# BaseModule_v8.net
KiCad netlist of a schematic drawn in EAGLE
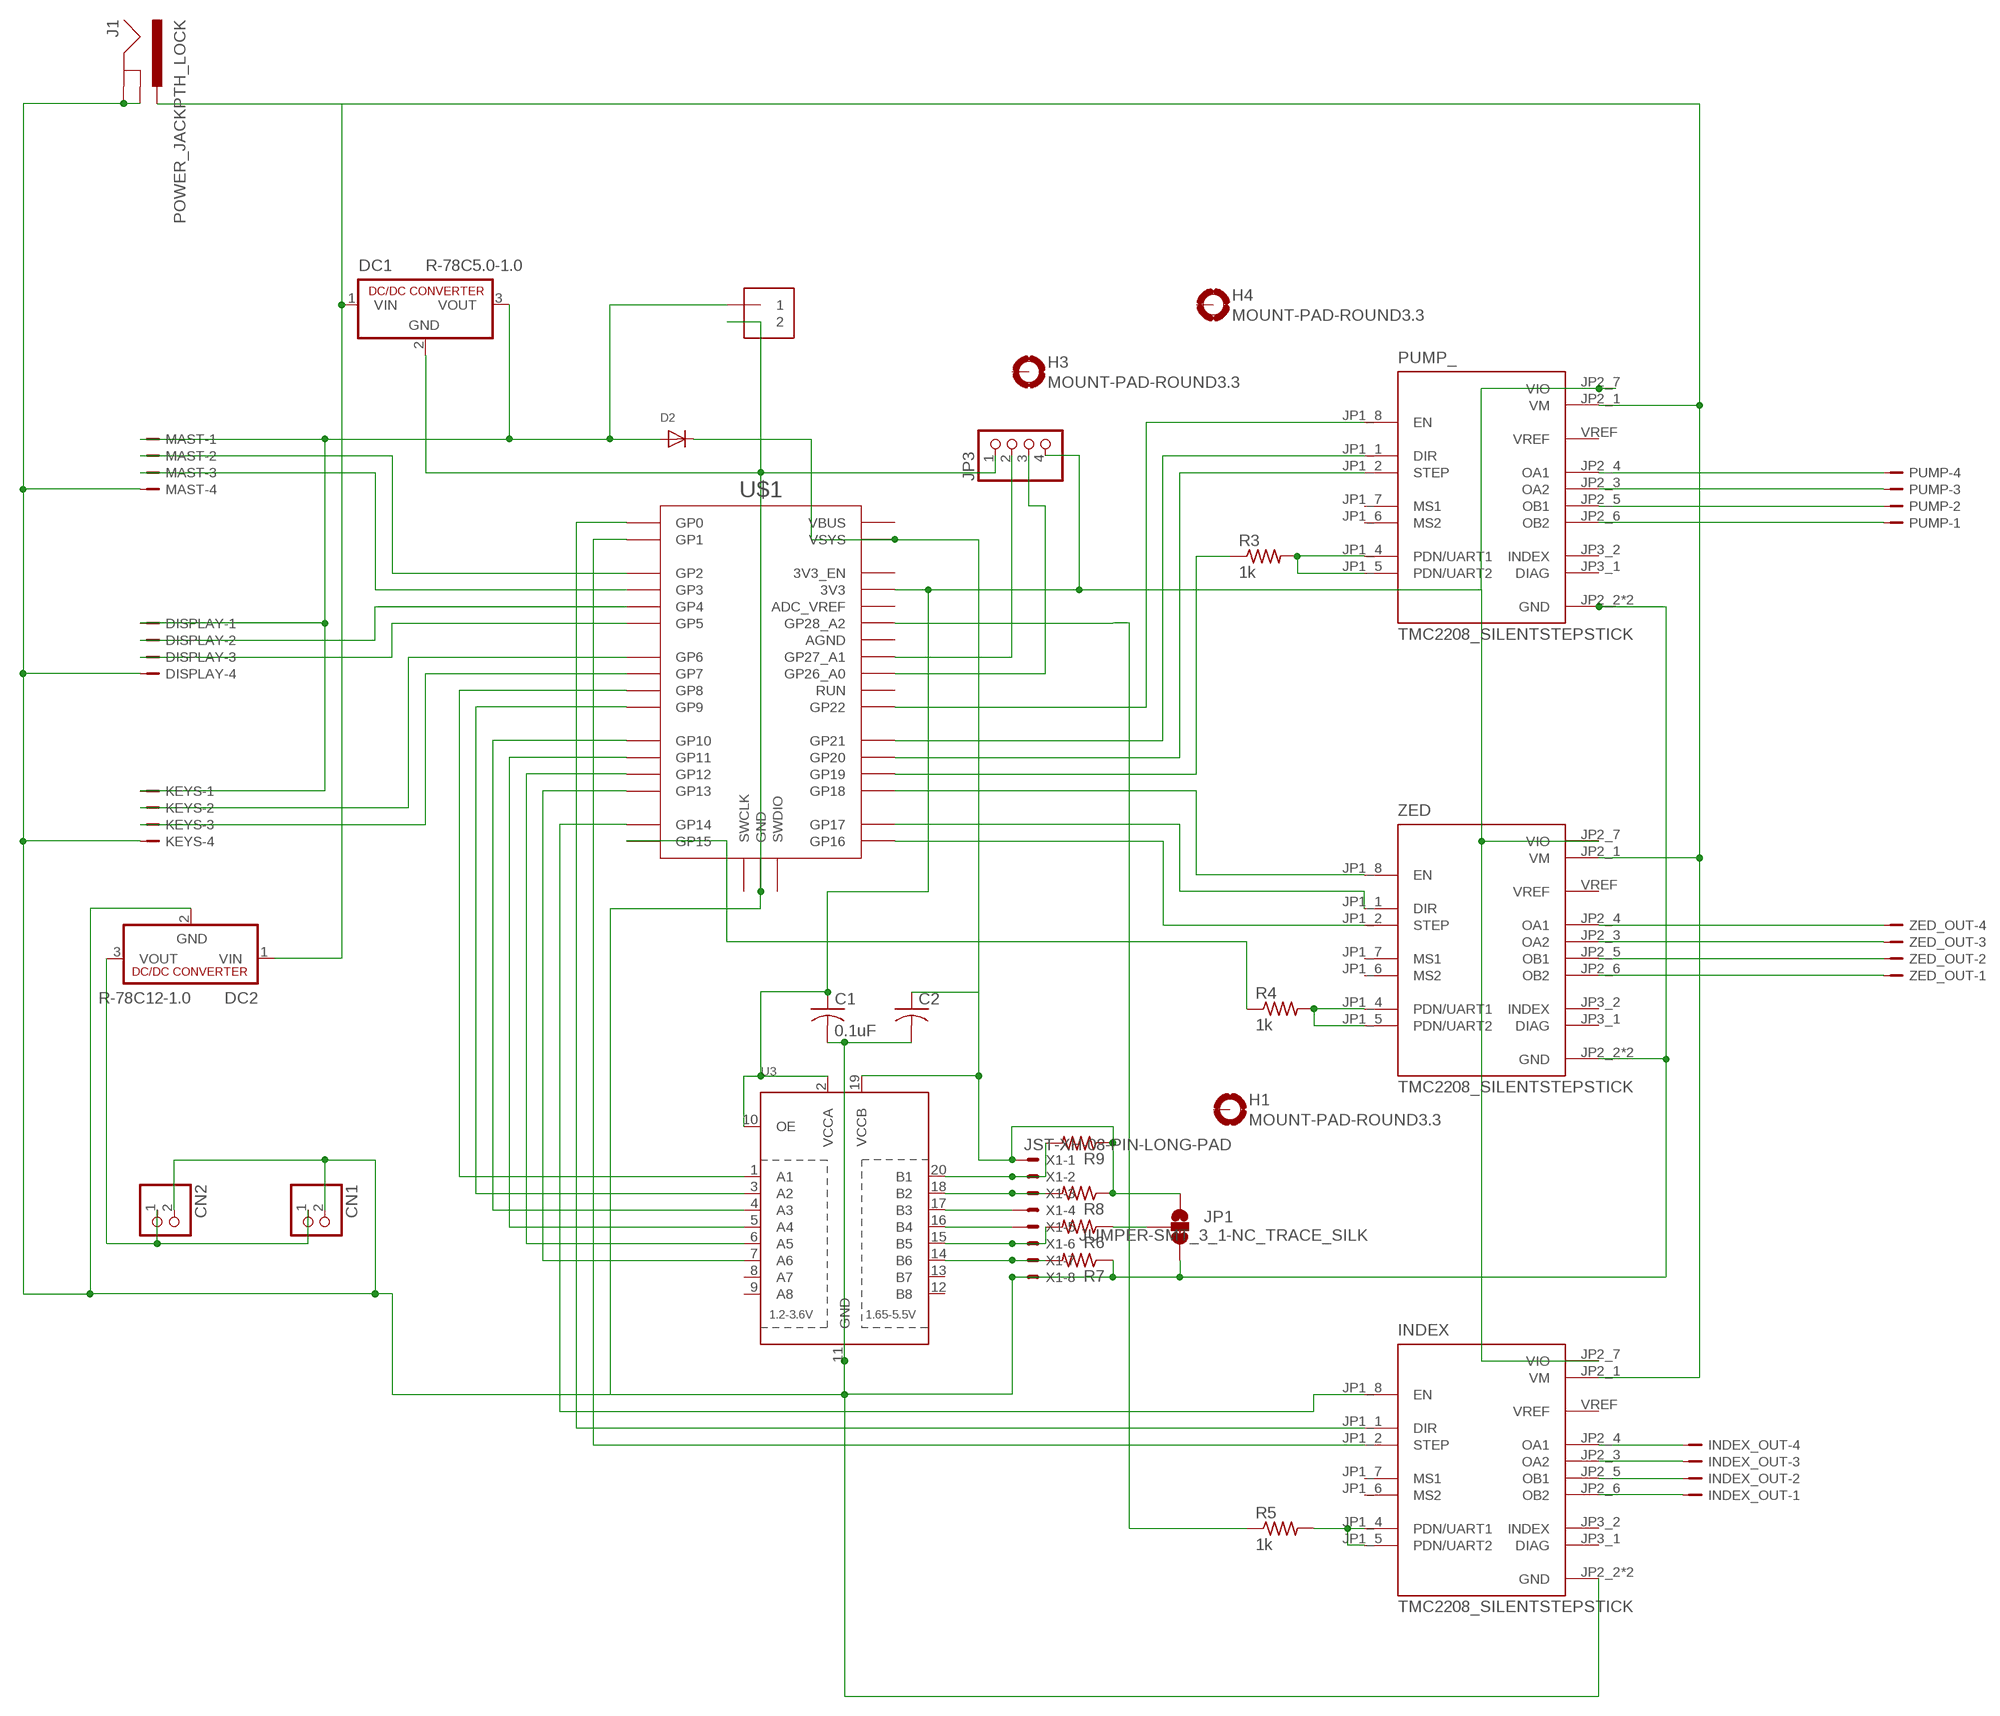
[diagram p0: schematic, sheet 1]

(export (version "E")
  (design (tool "Eeschema 10.0.6"))
  (components
    (comp (ref "C1")
      (value "0.1uF")
      (footprint "eagle-import:C1206")
      (libsource (lib "eagle-import") (part "C-USC1206"))
    )
    (comp (ref "C2")
      (value "C-USC1206")
      (footprint "eagle-import:C1206")
      (libsource (lib "eagle-import") (part "C-USC1206"))
    )
    (comp (ref "CN1")
      (value "JST_2PIN-THM-RA")
      (footprint "eagle-import:JST-PH-2-THM-RA")
      (libsource (lib "eagle-import") (part "JST_2PIN-THM-RA"))
    )
    (comp (ref "CN2")
      (value "JST_2PIN-THM-RA")
      (footprint "eagle-import:JST-PH-2-THM-RA")
      (libsource (lib "eagle-import") (part "JST_2PIN-THM-RA"))
    )
    (comp (ref "D2")
      (value "DIODESMA")
      (footprint "eagle-import:SMADIODE")
      (libsource (lib "eagle-import") (part "DIODESMA"))
    )
    (comp (ref "DC1")
      (value "R-78C5.0-1.0")
      (footprint "eagle-import:SIP3")
      (libsource (lib "eagle-import") (part "R-78C-1.05.0"))
    )
    (comp (ref "DC2")
      (value "R-78C12-1.0")
      (footprint "eagle-import:SIP3")
      (libsource (lib "eagle-import") (part "R-78C-1.012"))
    )
    (comp (ref "DISPLAY")
      (value "JST-PH-4_TH-V")
      (footprint "eagle-import:B4B-PH-K-S")
      (fields (field (name "MF") "JST") (field (name "MPN") "B4B-PH-K-S"))
      (libsource (lib "eagle-import") (part "JST-PH-4_TH-V"))
    )
    (comp (ref "H1")
      (value "MOUNT-PAD-ROUND3.3")
      (footprint "eagle-import:3,3-PAD")
      (libsource (lib "eagle-import") (part "MOUNT-PAD-ROUND3.3"))
    )
    (comp (ref "H3")
      (value "MOUNT-PAD-ROUND3.3")
      (footprint "eagle-import:3,3-PAD")
      (libsource (lib "eagle-import") (part "MOUNT-PAD-ROUND3.3"))
    )
    (comp (ref "H4")
      (value "MOUNT-PAD-ROUND3.3")
      (footprint "eagle-import:3,3-PAD")
      (libsource (lib "eagle-import") (part "MOUNT-PAD-ROUND3.3"))
    )
    (comp (ref "INDEX")
      (value "TMC2208_SILENTSTEPSTICK")
      (footprint "eagle-import:MODULE_TMC2208_SILENTSTEPSTICK")
      (fields (field (name "MF") "Trinamic Motion") (field (name "MP") "TMC2208 SILENTSTEPSTICK"))
      (libsource (lib "eagle-import") (part "TMC2208_SILENTSTEPSTICK"))
    )
    (comp (ref "INDEX_OUT")
      (value "JST-PH-4_TH-RA")
      (footprint "eagle-import:S4B-PH-KL")
      (fields (field (name "MF") "JST") (field (name "MPN") "S4B-PH-KL"))
      (libsource (lib "eagle-import") (part "JST-PH-4_TH-RA"))
    )
    (comp (ref "J1")
      (value "POWER_JACKPTH_LOCK")
      (footprint "eagle-import:POWER_JACK_PTH_LOCK")
      (libsource (lib "eagle-import") (part "POWER_JACKPTH_LOCK"))
    )
    (comp (ref "J2")
      (value "1X2-3.5MM")
      (footprint "eagle-import:1X2-3.5MM")
      (libsource (lib "eagle-import") (part "1X2-3.5MM"))
    )
    (comp (ref "JP1")
      (value "JUMPER-SMT_3_1-NC_TRACE_SILK")
      (footprint "eagle-import:SMT-JUMPER_3_1-NC_TRACE_SILK")
      (libsource (lib "eagle-import") (part "JUMPER-SMT_3_1-NC_TRACE_SILK"))
    )
    (comp (ref "JP3")
      (value "PINHD-1X4")
      (footprint "eagle-import:1X04")
      (libsource (lib "eagle-import") (part "PINHD-1X4"))
    )
    (comp (ref "KEYS")
      (value "JST-PH-4_TH-V")
      (footprint "eagle-import:B4B-PH-K-S")
      (fields (field (name "MF") "JST") (field (name "MPN") "B4B-PH-K-S"))
      (libsource (lib "eagle-import") (part "JST-PH-4_TH-V"))
    )
    (comp (ref "MAST")
      (value "JST-PH-4_TH-V")
      (footprint "eagle-import:B4B-PH-K-S")
      (fields (field (name "MF") "JST") (field (name "MPN") "B4B-PH-K-S"))
      (libsource (lib "eagle-import") (part "JST-PH-4_TH-V"))
    )
    (comp (ref "PUMP")
      (value "JST-PH-4_TH-RA")
      (footprint "eagle-import:S4B-PH-KL")
      (fields (field (name "MF") "JST") (field (name "MPN") "S4B-PH-KL"))
      (libsource (lib "eagle-import") (part "JST-PH-4_TH-RA"))
    )
    (comp (ref "PUMP_")
      (value "TMC2208_SILENTSTEPSTICK")
      (footprint "eagle-import:MODULE_TMC2208_SILENTSTEPSTICK")
      (fields (field (name "MF") "Trinamic Motion") (field (name "MP") "TMC2208 SILENTSTEPSTICK"))
      (libsource (lib "eagle-import") (part "TMC2208_SILENTSTEPSTICK"))
    )
    (comp (ref "R3")
      (value "1k")
      (footprint "eagle-import:R1206")
      (libsource (lib "eagle-import") (part "R-US_R1206"))
    )
    (comp (ref "R4")
      (value "1k")
      (footprint "eagle-import:R1206")
      (libsource (lib "eagle-import") (part "R-US_R1206"))
    )
    (comp (ref "R5")
      (value "1k")
      (footprint "eagle-import:R1206")
      (libsource (lib "eagle-import") (part "R-US_R1206"))
    )
    (comp (ref "R6")
      (value "R-US_M1206")
      (footprint "eagle-import:M1206")
      (libsource (lib "eagle-import") (part "R-US_M1206"))
    )
    (comp (ref "R7")
      (value "R-US_M1206")
      (footprint "eagle-import:M1206")
      (libsource (lib "eagle-import") (part "R-US_M1206"))
    )
    (comp (ref "R8")
      (value "R-US_M1206")
      (footprint "eagle-import:M1206")
      (libsource (lib "eagle-import") (part "R-US_M1206"))
    )
    (comp (ref "R9")
      (value "R-US_M1206")
      (footprint "eagle-import:M1206")
      (libsource (lib "eagle-import") (part "R-US_M1206"))
    )
    (comp (ref "U$1")
      (value "RPI_PICO-TH")
      (footprint "eagle-import:RPI_PICO_TH")
      (libsource (lib "eagle-import") (part "RPI_PICO-TH"))
    )
    (comp (ref "U3")
      (value "TXB0108PWR")
      (footprint "eagle-import:TSSOP20")
      (libsource (lib "eagle-import") (part "TXB0108PWR"))
    )
    (comp (ref "X1")
      (value "JST-XH-08-PIN-LONG-PAD")
      (footprint "eagle-import:JST-XH-08-PACKAGE-LONG-PAD")
      (libsource (lib "eagle-import") (part "JST-XH-08-PIN-LONG-PAD"))
    )
    (comp (ref "ZED")
      (value "TMC2208_SILENTSTEPSTICK")
      (footprint "eagle-import:MODULE_TMC2208_SILENTSTEPSTICK")
      (fields (field (name "MF") "Trinamic Motion") (field (name "MP") "TMC2208 SILENTSTEPSTICK"))
      (libsource (lib "eagle-import") (part "TMC2208_SILENTSTEPSTICK"))
    )
    (comp (ref "ZED_OUT")
      (value "JST-PH-4_TH-RA")
      (footprint "eagle-import:S4B-PH-KL")
      (fields (field (name "MF") "JST") (field (name "MPN") "S4B-PH-KL"))
      (libsource (lib "eagle-import") (part "JST-PH-4_TH-RA"))
    )
  )
  (nets
    (net (code "1") (name "Net-(CN1-1)") (class "Default")
      (node (ref "C1") (pin "2") (pinfunction "2_2") (pintype "passive"))
      (node (ref "C2") (pin "2") (pinfunction "2_2") (pintype "passive"))
      (node (ref "CN1") (pin "2") (pinfunction "1_2") (pintype "passive"))
      (node (ref "CN2") (pin "2") (pinfunction "1_2") (pintype "passive"))
      (node (ref "DC1") (pin "2") (pinfunction "GND_2") (pintype "passive"))
      (node (ref "DC2") (pin "2") (pinfunction "GND_2") (pintype "passive"))
      (node (ref "DISPLAY") (pin "4") (pinfunction "1_4") (pintype "passive"))
      (node (ref "INDEX") (pin "JP2_2") (pinfunction "GND_JP2_2") (pintype "power_in"))
      (node (ref "INDEX") (pin "JP2_8") (pinfunction "GND_JP2_8") (pintype "power_in"))
      (node (ref "J1") (pin "GND") (pinfunction "GND_GND") (pintype "bidirectional"))
      (node (ref "J1") (pin "GNDBREAK") (pinfunction "GNDBREAK_GNDBREAK") (pintype "bidirectional"))
      (node (ref "J2") (pin "2") (pinfunction "2_2") (pintype "passive"))
      (node (ref "JP1") (pin "3") (pinfunction "3_3") (pintype "passive"))
      (node (ref "JP3") (pin "1") (pinfunction "1_1") (pintype "passive"))
      (node (ref "KEYS") (pin "4") (pinfunction "1_4") (pintype "passive"))
      (node (ref "MAST") (pin "4") (pinfunction "1_4") (pintype "passive"))
      (node (ref "PUMP_") (pin "JP2_2") (pinfunction "GND_JP2_2") (pintype "power_in"))
      (node (ref "PUMP_") (pin "JP2_8") (pinfunction "GND_JP2_8") (pintype "power_in"))
      (node (ref "R7") (pin "1") (pinfunction "1_1") (pintype "passive"))
      (node (ref "U$1") (pin "GND@1") (pinfunction "GND_GND@1") (pintype "bidirectional"))
      (node (ref "U$1") (pin "GND@2") (pinfunction "GND_GND@2") (pintype "bidirectional"))
      (node (ref "U$1") (pin "GND@3") (pinfunction "GND_GND@3") (pintype "bidirectional"))
      (node (ref "U$1") (pin "GND@4") (pinfunction "GND_GND@4") (pintype "bidirectional"))
      (node (ref "U$1") (pin "GND@5") (pinfunction "GND_GND@5") (pintype "bidirectional"))
      (node (ref "U$1") (pin "GND@6") (pinfunction "GND_GND@6") (pintype "bidirectional"))
      (node (ref "U$1") (pin "GND@7") (pinfunction "GND_GND@7") (pintype "bidirectional"))
      (node (ref "U$1") (pin "GND@8") (pinfunction "GND_GND@8") (pintype "bidirectional"))
      (node (ref "U3") (pin "11") (pinfunction "GND_11") (pintype "bidirectional"))
      (node (ref "X1") (pin "8") (pinfunction "S_8") (pintype "passive"))
      (node (ref "ZED") (pin "JP2_2") (pinfunction "GND_JP2_2") (pintype "power_in"))
      (node (ref "ZED") (pin "JP2_8") (pinfunction "GND_JP2_8") (pintype "power_in"))
    )
    (net (code "2") (name "Net-(CN1-2)") (class "Default")
      (node (ref "CN1") (pin "1") (pinfunction "2_1") (pintype "passive"))
      (node (ref "CN2") (pin "1") (pinfunction "2_1") (pintype "passive"))
      (node (ref "DC2") (pin "3") (pinfunction "VOUT_3") (pintype "passive"))
    )
    (net (code "3") (name "Net-(DC1-VIN)") (class "Default")
      (node (ref "DC1") (pin "1") (pinfunction "VIN_1") (pintype "passive"))
      (node (ref "DC2") (pin "1") (pinfunction "VIN_1") (pintype "passive"))
      (node (ref "INDEX") (pin "JP2_1") (pinfunction "VM_JP2_1") (pintype "power_in"))
      (node (ref "J1") (pin "PWR") (pinfunction "PWR_PWR") (pintype "bidirectional"))
      (node (ref "PUMP_") (pin "JP2_1") (pinfunction "VM_JP2_1") (pintype "power_in"))
      (node (ref "ZED") (pin "JP2_1") (pinfunction "VM_JP2_1") (pintype "power_in"))
    )
    (net (code "4") (name "Net-(DC1-VOUT)") (class "Default")
      (node (ref "D2") (pin "A") (pinfunction "A_A") (pintype "passive"))
      (node (ref "DC1") (pin "3") (pinfunction "VOUT_3") (pintype "passive"))
      (node (ref "DISPLAY") (pin "1") (pinfunction "1_1") (pintype "passive"))
      (node (ref "J2") (pin "1") (pinfunction "1_1") (pintype "passive"))
      (node (ref "KEYS") (pin "1") (pinfunction "1_1") (pintype "passive"))
      (node (ref "MAST") (pin "1") (pinfunction "1_1") (pintype "passive"))
    )
    (net (code "5") (name "Net-(DISPLAYB-1)") (class "Default")
      (node (ref "DISPLAY") (pin "2") (pinfunction "1_2") (pintype "passive"))
      (node (ref "U$1") (pin "GP4") (pinfunction "GP4_GP4") (pintype "bidirectional"))
    )
    (net (code "6") (name "Net-(DISPLAYC-1)") (class "Default")
      (node (ref "DISPLAY") (pin "3") (pinfunction "1_3") (pintype "passive"))
      (node (ref "U$1") (pin "GP5") (pinfunction "GP5_GP5") (pintype "bidirectional"))
    )
    (net (code "7") (name "Net-(INDEX-DIR)") (class "Default")
      (node (ref "INDEX") (pin "JP1_1") (pinfunction "DIR_JP1_1") (pintype "input"))
      (node (ref "U$1") (pin "GP0") (pinfunction "GP0_GP0") (pintype "bidirectional"))
    )
    (net (code "8") (name "Net-(INDEX-EN)") (class "Default")
      (node (ref "INDEX") (pin "JP1_8") (pinfunction "EN_JP1_8") (pintype "input"))
      (node (ref "U$1") (pin "GP14") (pinfunction "GP14_GP14") (pintype "bidirectional"))
    )
    (net (code "9") (name "Net-(INDEX-OA1)") (class "Default")
      (node (ref "INDEX") (pin "JP2_4") (pinfunction "OA1_JP2_4") (pintype "passive"))
      (node (ref "INDEX_OUT") (pin "4") (pinfunction "1_4") (pintype "passive"))
    )
    (net (code "10") (name "Net-(INDEX-OA2)") (class "Default")
      (node (ref "INDEX") (pin "JP2_3") (pinfunction "OA2_JP2_3") (pintype "passive"))
      (node (ref "INDEX_OUT") (pin "3") (pinfunction "1_3") (pintype "passive"))
    )
    (net (code "11") (name "Net-(INDEX-OB1)") (class "Default")
      (node (ref "INDEX") (pin "JP2_5") (pinfunction "OB1_JP2_5") (pintype "passive"))
      (node (ref "INDEX_OUT") (pin "2") (pinfunction "1_2") (pintype "passive"))
    )
    (net (code "12") (name "Net-(INDEX-OB2)") (class "Default")
      (node (ref "INDEX") (pin "JP2_6") (pinfunction "OB2_JP2_6") (pintype "passive"))
      (node (ref "INDEX_OUT") (pin "1") (pinfunction "1_1") (pintype "passive"))
    )
    (net (code "13") (name "Net-(INDEX-PDN{slash}UART1)") (class "Default")
      (node (ref "INDEX") (pin "JP1_4") (pinfunction "PDN/UART1_JP1_4") (pintype "bidirectional"))
      (node (ref "INDEX") (pin "JP1_5") (pinfunction "PDN/UART2_JP1_5") (pintype "bidirectional"))
      (node (ref "R5") (pin "2") (pinfunction "2_2") (pintype "passive"))
    )
    (net (code "14") (name "Net-(INDEX-STEP)") (class "Default")
      (node (ref "INDEX") (pin "JP1_2") (pinfunction "STEP_JP1_2") (pintype "input"))
      (node (ref "U$1") (pin "GP1") (pinfunction "GP1_GP1") (pintype "bidirectional"))
    )
    (net (code "15") (name "Net-(INDEX-VIO)") (class "Default")
      (node (ref "C1") (pin "1") (pinfunction "1_1") (pintype "passive"))
      (node (ref "INDEX") (pin "JP2_7") (pinfunction "VIO_JP2_7") (pintype "power_in"))
      (node (ref "JP3") (pin "4") (pinfunction "4_4") (pintype "passive"))
      (node (ref "PUMP_") (pin "JP2_7") (pinfunction "VIO_JP2_7") (pintype "power_in"))
      (node (ref "U$1") (pin "3V3") (pinfunction "3V3_3V3") (pintype "bidirectional"))
      (node (ref "U3") (pin "10") (pinfunction "OE_10") (pintype "bidirectional"))
      (node (ref "U3") (pin "2") (pinfunction "VCCA_2") (pintype "bidirectional"))
      (node (ref "ZED") (pin "JP2_7") (pinfunction "VIO_JP2_7") (pintype "power_in"))
    )
    (net (code "16") (name "Net-(JP1-Pad2)") (class "Default")
      (node (ref "JP1") (pin "2") (pinfunction "2_2") (pintype "passive"))
      (node (ref "R6") (pin "1") (pinfunction "1_1") (pintype "passive"))
    )
    (net (code "17") (name "Net-(JP3-Pad2)") (class "Default")
      (node (ref "JP3") (pin "2") (pinfunction "2_2") (pintype "passive"))
      (node (ref "U$1") (pin "GP27_A1") (pinfunction "GP27_A1_GP27_A1") (pintype "bidirectional"))
    )
    (net (code "18") (name "Net-(JP3-Pad3)") (class "Default")
      (node (ref "JP3") (pin "3") (pinfunction "3_3") (pintype "passive"))
      (node (ref "U$1") (pin "GP26_A0") (pinfunction "GP26_A0_GP26_A0") (pintype "bidirectional"))
    )
    (net (code "19") (name "Net-(KEYSB-1)") (class "Default")
      (node (ref "KEYS") (pin "2") (pinfunction "1_2") (pintype "passive"))
      (node (ref "U$1") (pin "GP6") (pinfunction "GP6_GP6") (pintype "bidirectional"))
    )
    (net (code "20") (name "Net-(KEYSC-1)") (class "Default")
      (node (ref "KEYS") (pin "3") (pinfunction "1_3") (pintype "passive"))
      (node (ref "U$1") (pin "GP7") (pinfunction "GP7_GP7") (pintype "bidirectional"))
    )
    (net (code "21") (name "Net-(MASTB-1)") (class "Default")
      (node (ref "MAST") (pin "2") (pinfunction "1_2") (pintype "passive"))
      (node (ref "U$1") (pin "GP2") (pinfunction "GP2_GP2") (pintype "bidirectional"))
    )
    (net (code "22") (name "Net-(MASTC-1)") (class "Default")
      (node (ref "MAST") (pin "3") (pinfunction "1_3") (pintype "passive"))
      (node (ref "U$1") (pin "GP3") (pinfunction "GP3_GP3") (pintype "bidirectional"))
    )
    (net (code "23") (name "Net-(PUMPB-1)") (class "Default")
      (node (ref "PUMP") (pin "2") (pinfunction "1_2") (pintype "passive"))
      (node (ref "PUMP_") (pin "JP2_5") (pinfunction "OB1_JP2_5") (pintype "passive"))
    )
    (net (code "24") (name "Net-(PUMPC-1)") (class "Default")
      (node (ref "PUMP") (pin "3") (pinfunction "1_3") (pintype "passive"))
      (node (ref "PUMP_") (pin "JP2_3") (pinfunction "OA2_JP2_3") (pintype "passive"))
    )
    (net (code "25") (name "Net-(PUMPD-1)") (class "Default")
      (node (ref "PUMP") (pin "4") (pinfunction "1_4") (pintype "passive"))
      (node (ref "PUMP_") (pin "JP2_4") (pinfunction "OA1_JP2_4") (pintype "passive"))
    )
    (net (code "26") (name "Net-(PUMP_-DIR)") (class "Default")
      (node (ref "PUMP_") (pin "JP1_1") (pinfunction "DIR_JP1_1") (pintype "input"))
      (node (ref "U$1") (pin "GP21") (pinfunction "GP21_GP21") (pintype "bidirectional"))
    )
    (net (code "27") (name "Net-(PUMP_-EN)") (class "Default")
      (node (ref "PUMP_") (pin "JP1_8") (pinfunction "EN_JP1_8") (pintype "input"))
      (node (ref "U$1") (pin "GP22") (pinfunction "GP22_GP22") (pintype "bidirectional"))
    )
    (net (code "28") (name "Net-(PUMP_-OB2)") (class "Default")
      (node (ref "PUMP") (pin "1") (pinfunction "1_1") (pintype "passive"))
      (node (ref "PUMP_") (pin "JP2_6") (pinfunction "OB2_JP2_6") (pintype "passive"))
    )
    (net (code "29") (name "Net-(PUMP_-PDN{slash}UART1)") (class "Default")
      (node (ref "PUMP_") (pin "JP1_4") (pinfunction "PDN/UART1_JP1_4") (pintype "bidirectional"))
      (node (ref "PUMP_") (pin "JP1_5") (pinfunction "PDN/UART2_JP1_5") (pintype "bidirectional"))
      (node (ref "R3") (pin "2") (pinfunction "2_2") (pintype "passive"))
    )
    (net (code "30") (name "Net-(PUMP_-STEP)") (class "Default")
      (node (ref "PUMP_") (pin "JP1_2") (pinfunction "STEP_JP1_2") (pintype "input"))
      (node (ref "U$1") (pin "GP20") (pinfunction "GP20_GP20") (pintype "bidirectional"))
    )
    (net (code "31") (name "Net-(R3-Pad1)") (class "Default")
      (node (ref "R3") (pin "1") (pinfunction "1_1") (pintype "passive"))
      (node (ref "U$1") (pin "GP19") (pinfunction "GP19_GP19") (pintype "bidirectional"))
    )
    (net (code "32") (name "Net-(R4-Pad1)") (class "Default")
      (node (ref "R4") (pin "1") (pinfunction "1_1") (pintype "passive"))
      (node (ref "U$1") (pin "GP15") (pinfunction "GP15_GP15") (pintype "bidirectional"))
    )
    (net (code "33") (name "Net-(R5-Pad1)") (class "Default")
      (node (ref "R5") (pin "1") (pinfunction "1_1") (pintype "passive"))
      (node (ref "U$1") (pin "GP28_A2") (pinfunction "GP28_A2_GP28_A2") (pintype "bidirectional"))
    )
    (net (code "34") (name "Net-(U3-A1)") (class "Default")
      (node (ref "U$1") (pin "GP8") (pinfunction "GP8_GP8") (pintype "bidirectional"))
      (node (ref "U3") (pin "1") (pinfunction "A1_1") (pintype "bidirectional"))
    )
    (net (code "35") (name "Net-(U3-A2)") (class "Default")
      (node (ref "U$1") (pin "GP9") (pinfunction "GP9_GP9") (pintype "bidirectional"))
      (node (ref "U3") (pin "3") (pinfunction "A2_3") (pintype "bidirectional"))
    )
    (net (code "36") (name "Net-(U3-A3)") (class "Default")
      (node (ref "U$1") (pin "GP10") (pinfunction "GP10_GP10") (pintype "bidirectional"))
      (node (ref "U3") (pin "4") (pinfunction "A3_4") (pintype "bidirectional"))
    )
    (net (code "37") (name "Net-(U3-A4)") (class "Default")
      (node (ref "U$1") (pin "GP11") (pinfunction "GP11_GP11") (pintype "bidirectional"))
      (node (ref "U3") (pin "5") (pinfunction "A4_5") (pintype "bidirectional"))
    )
    (net (code "38") (name "Net-(U3-A5)") (class "Default")
      (node (ref "U$1") (pin "GP12") (pinfunction "GP12_GP12") (pintype "bidirectional"))
      (node (ref "U3") (pin "6") (pinfunction "A5_6") (pintype "bidirectional"))
    )
    (net (code "39") (name "Net-(U3-A6)") (class "Default")
      (node (ref "U$1") (pin "GP13") (pinfunction "GP13_GP13") (pintype "bidirectional"))
      (node (ref "U3") (pin "7") (pinfunction "A6_7") (pintype "bidirectional"))
    )
    (net (code "40") (name "Net-(U3-B1)") (class "Default")
      (node (ref "R9") (pin "2") (pinfunction "2_2") (pintype "passive"))
      (node (ref "U3") (pin "20") (pinfunction "B1_20") (pintype "bidirectional"))
      (node (ref "X1") (pin "2") (pinfunction "S_2") (pintype "passive"))
    )
    (net (code "41") (name "Net-(U3-B2)") (class "Default")
      (node (ref "R8") (pin "2") (pinfunction "2_2") (pintype "passive"))
      (node (ref "U3") (pin "18") (pinfunction "B2_18") (pintype "bidirectional"))
      (node (ref "X1") (pin "3") (pinfunction "S_3") (pintype "passive"))
    )
    (net (code "42") (name "Net-(U3-B3)") (class "Default")
      (node (ref "U3") (pin "17") (pinfunction "B3_17") (pintype "bidirectional"))
      (node (ref "X1") (pin "4") (pinfunction "S_4") (pintype "passive"))
    )
    (net (code "43") (name "Net-(U3-B4)") (class "Default")
      (node (ref "U3") (pin "16") (pinfunction "B4_16") (pintype "bidirectional"))
      (node (ref "X1") (pin "5") (pinfunction "S_5") (pintype "passive"))
    )
    (net (code "44") (name "Net-(U3-B5)") (class "Default")
      (node (ref "R6") (pin "2") (pinfunction "2_2") (pintype "passive"))
      (node (ref "U3") (pin "15") (pinfunction "B5_15") (pintype "bidirectional"))
      (node (ref "X1") (pin "6") (pinfunction "S_6") (pintype "passive"))
    )
    (net (code "45") (name "Net-(U3-B6)") (class "Default")
      (node (ref "R7") (pin "2") (pinfunction "2_2") (pintype "passive"))
      (node (ref "U3") (pin "14") (pinfunction "B6_14") (pintype "bidirectional"))
      (node (ref "X1") (pin "7") (pinfunction "S_7") (pintype "passive"))
    )
    (net (code "46") (name "Net-(U3-VCCB)") (class "Default")
      (node (ref "C2") (pin "1") (pinfunction "1_1") (pintype "passive"))
      (node (ref "D2") (pin "C") (pinfunction "C_C") (pintype "passive"))
      (node (ref "JP1") (pin "1") (pinfunction "1_1") (pintype "passive"))
      (node (ref "R8") (pin "1") (pinfunction "1_1") (pintype "passive"))
      (node (ref "R9") (pin "1") (pinfunction "1_1") (pintype "passive"))
      (node (ref "U$1") (pin "VSYS") (pinfunction "VSYS_VSYS") (pintype "bidirectional"))
      (node (ref "U3") (pin "19") (pinfunction "VCCB_19") (pintype "bidirectional"))
      (node (ref "X1") (pin "1") (pinfunction "S_1") (pintype "passive"))
    )
    (net (code "47") (name "Net-(ZED-DIR)") (class "Default")
      (node (ref "U$1") (pin "GP17") (pinfunction "GP17_GP17") (pintype "bidirectional"))
      (node (ref "ZED") (pin "JP1_1") (pinfunction "DIR_JP1_1") (pintype "input"))
    )
    (net (code "48") (name "Net-(ZED-EN)") (class "Default")
      (node (ref "U$1") (pin "GP18") (pinfunction "GP18_GP18") (pintype "bidirectional"))
      (node (ref "ZED") (pin "JP1_8") (pinfunction "EN_JP1_8") (pintype "input"))
    )
    (net (code "49") (name "Net-(ZED-OA1)") (class "Default")
      (node (ref "ZED") (pin "JP2_4") (pinfunction "OA1_JP2_4") (pintype "passive"))
      (node (ref "ZED_OUT") (pin "4") (pinfunction "1_4") (pintype "passive"))
    )
    (net (code "50") (name "Net-(ZED-OA2)") (class "Default")
      (node (ref "ZED") (pin "JP2_3") (pinfunction "OA2_JP2_3") (pintype "passive"))
      (node (ref "ZED_OUT") (pin "3") (pinfunction "1_3") (pintype "passive"))
    )
    (net (code "51") (name "Net-(ZED-OB1)") (class "Default")
      (node (ref "ZED") (pin "JP2_5") (pinfunction "OB1_JP2_5") (pintype "passive"))
      (node (ref "ZED_OUT") (pin "2") (pinfunction "1_2") (pintype "passive"))
    )
    (net (code "52") (name "Net-(ZED-OB2)") (class "Default")
      (node (ref "ZED") (pin "JP2_6") (pinfunction "OB2_JP2_6") (pintype "passive"))
      (node (ref "ZED_OUT") (pin "1") (pinfunction "1_1") (pintype "passive"))
    )
    (net (code "53") (name "Net-(ZED-PDN{slash}UART1)") (class "Default")
      (node (ref "R4") (pin "2") (pinfunction "2_2") (pintype "passive"))
      (node (ref "ZED") (pin "JP1_4") (pinfunction "PDN/UART1_JP1_4") (pintype "bidirectional"))
      (node (ref "ZED") (pin "JP1_5") (pinfunction "PDN/UART2_JP1_5") (pintype "bidirectional"))
    )
    (net (code "54") (name "Net-(ZED-STEP)") (class "Default")
      (node (ref "U$1") (pin "GP16") (pinfunction "GP16_GP16") (pintype "bidirectional"))
      (node (ref "ZED") (pin "JP1_2") (pinfunction "STEP_JP1_2") (pintype "input"))
    )
    (net (code "55") (name "unconnected-(H1-MOUNT-PadB3,3)") (class "Default")
      (node (ref "H1") (pin "B3,3") (pinfunction "MOUNT_B3,3") (pintype "passive"))
    )
    (net (code "56") (name "unconnected-(H3-MOUNT-PadB3,3)") (class "Default")
      (node (ref "H3") (pin "B3,3") (pinfunction "MOUNT_B3,3") (pintype "passive"))
    )
    (net (code "57") (name "unconnected-(H4-MOUNT-PadB3,3)") (class "Default")
      (node (ref "H4") (pin "B3,3") (pinfunction "MOUNT_B3,3") (pintype "passive"))
    )
    (net (code "58") (name "unconnected-(INDEX-DIAG-PadJP3_1)") (class "Default")
      (node (ref "INDEX") (pin "JP3_1") (pinfunction "DIAG_JP3_1") (pintype "output"))
    )
    (net (code "59") (name "unconnected-(INDEX-INDEX-PadJP3_2)") (class "Default")
      (node (ref "INDEX") (pin "JP3_2") (pinfunction "INDEX_JP3_2") (pintype "output"))
    )
    (net (code "60") (name "unconnected-(INDEX-MS1-PadJP1_7)") (class "Default")
      (node (ref "INDEX") (pin "JP1_7") (pinfunction "MS1_JP1_7") (pintype "input"))
    )
    (net (code "61") (name "unconnected-(INDEX-MS2-PadJP1_6)") (class "Default")
      (node (ref "INDEX") (pin "JP1_6") (pinfunction "MS2_JP1_6") (pintype "input"))
    )
    (net (code "62") (name "unconnected-(INDEX-PadVREF)") (class "Default")
      (node (ref "INDEX") (pin "VREF") (pinfunction "VREF_VREF") (pintype "passive"))
    )
    (net (code "63") (name "unconnected-(PUMP_-DIAG-PadJP3_1)") (class "Default")
      (node (ref "PUMP_") (pin "JP3_1") (pinfunction "DIAG_JP3_1") (pintype "output"))
    )
    (net (code "64") (name "unconnected-(PUMP_-INDEX-PadJP3_2)") (class "Default")
      (node (ref "PUMP_") (pin "JP3_2") (pinfunction "INDEX_JP3_2") (pintype "output"))
    )
    (net (code "65") (name "unconnected-(PUMP_-MS1-PadJP1_7)") (class "Default")
      (node (ref "PUMP_") (pin "JP1_7") (pinfunction "MS1_JP1_7") (pintype "input"))
    )
    (net (code "66") (name "unconnected-(PUMP_-MS2-PadJP1_6)") (class "Default")
      (node (ref "PUMP_") (pin "JP1_6") (pinfunction "MS2_JP1_6") (pintype "input"))
    )
    (net (code "67") (name "unconnected-(PUMP_-PadVREF)") (class "Default")
      (node (ref "PUMP_") (pin "VREF") (pinfunction "VREF_VREF") (pintype "passive"))
    )
    (net (code "68") (name "unconnected-(U$1-Pad3V3_EN)") (class "Default")
      (node (ref "U$1") (pin "3V3_EN") (pinfunction "3V3_EN_3V3_EN") (pintype "bidirectional"))
    )
    (net (code "69") (name "unconnected-(U$1-PadADC_VREF)") (class "Default")
      (node (ref "U$1") (pin "ADC_VREF") (pinfunction "ADC_VREF_ADC_VREF") (pintype "bidirectional"))
    )
    (net (code "70") (name "unconnected-(U$1-PadAGND)") (class "Default")
      (node (ref "U$1") (pin "AGND") (pinfunction "AGND_AGND") (pintype "bidirectional"))
    )
    (net (code "71") (name "unconnected-(U$1-PadRUN)") (class "Default")
      (node (ref "U$1") (pin "RUN") (pinfunction "RUN_RUN") (pintype "bidirectional"))
    )
    (net (code "72") (name "unconnected-(U$1-PadSWCLK)") (class "Default")
      (node (ref "U$1") (pin "SWCLK") (pinfunction "SWCLK_SWCLK") (pintype "bidirectional"))
    )
    (net (code "73") (name "unconnected-(U$1-PadSWDIO)") (class "Default")
      (node (ref "U$1") (pin "SWDIO") (pinfunction "SWDIO_SWDIO") (pintype "bidirectional"))
    )
    (net (code "74") (name "unconnected-(U$1-PadVBUS)") (class "Default")
      (node (ref "U$1") (pin "VBUS") (pinfunction "VBUS_VBUS") (pintype "bidirectional"))
    )
    (net (code "75") (name "unconnected-(U3-A7-Pad8)") (class "Default")
      (node (ref "U3") (pin "8") (pinfunction "A7_8") (pintype "bidirectional"))
    )
    (net (code "76") (name "unconnected-(U3-A8-Pad9)") (class "Default")
      (node (ref "U3") (pin "9") (pinfunction "A8_9") (pintype "bidirectional"))
    )
    (net (code "77") (name "unconnected-(U3-B7-Pad13)") (class "Default")
      (node (ref "U3") (pin "13") (pinfunction "B7_13") (pintype "bidirectional"))
    )
    (net (code "78") (name "unconnected-(U3-B8-Pad12)") (class "Default")
      (node (ref "U3") (pin "12") (pinfunction "B8_12") (pintype "bidirectional"))
    )
    (net (code "79") (name "unconnected-(ZED-DIAG-PadJP3_1)") (class "Default")
      (node (ref "ZED") (pin "JP3_1") (pinfunction "DIAG_JP3_1") (pintype "output"))
    )
    (net (code "80") (name "unconnected-(ZED-INDEX-PadJP3_2)") (class "Default")
      (node (ref "ZED") (pin "JP3_2") (pinfunction "INDEX_JP3_2") (pintype "output"))
    )
    (net (code "81") (name "unconnected-(ZED-MS1-PadJP1_7)") (class "Default")
      (node (ref "ZED") (pin "JP1_7") (pinfunction "MS1_JP1_7") (pintype "input"))
    )
    (net (code "82") (name "unconnected-(ZED-MS2-PadJP1_6)") (class "Default")
      (node (ref "ZED") (pin "JP1_6") (pinfunction "MS2_JP1_6") (pintype "input"))
    )
    (net (code "83") (name "unconnected-(ZED-PadVREF)") (class "Default")
      (node (ref "ZED") (pin "VREF") (pinfunction "VREF_VREF") (pintype "passive"))
    )
  )
)
